# Uchicha.net
KiCad netlist of a schematic drawn in EasyEDA Pro
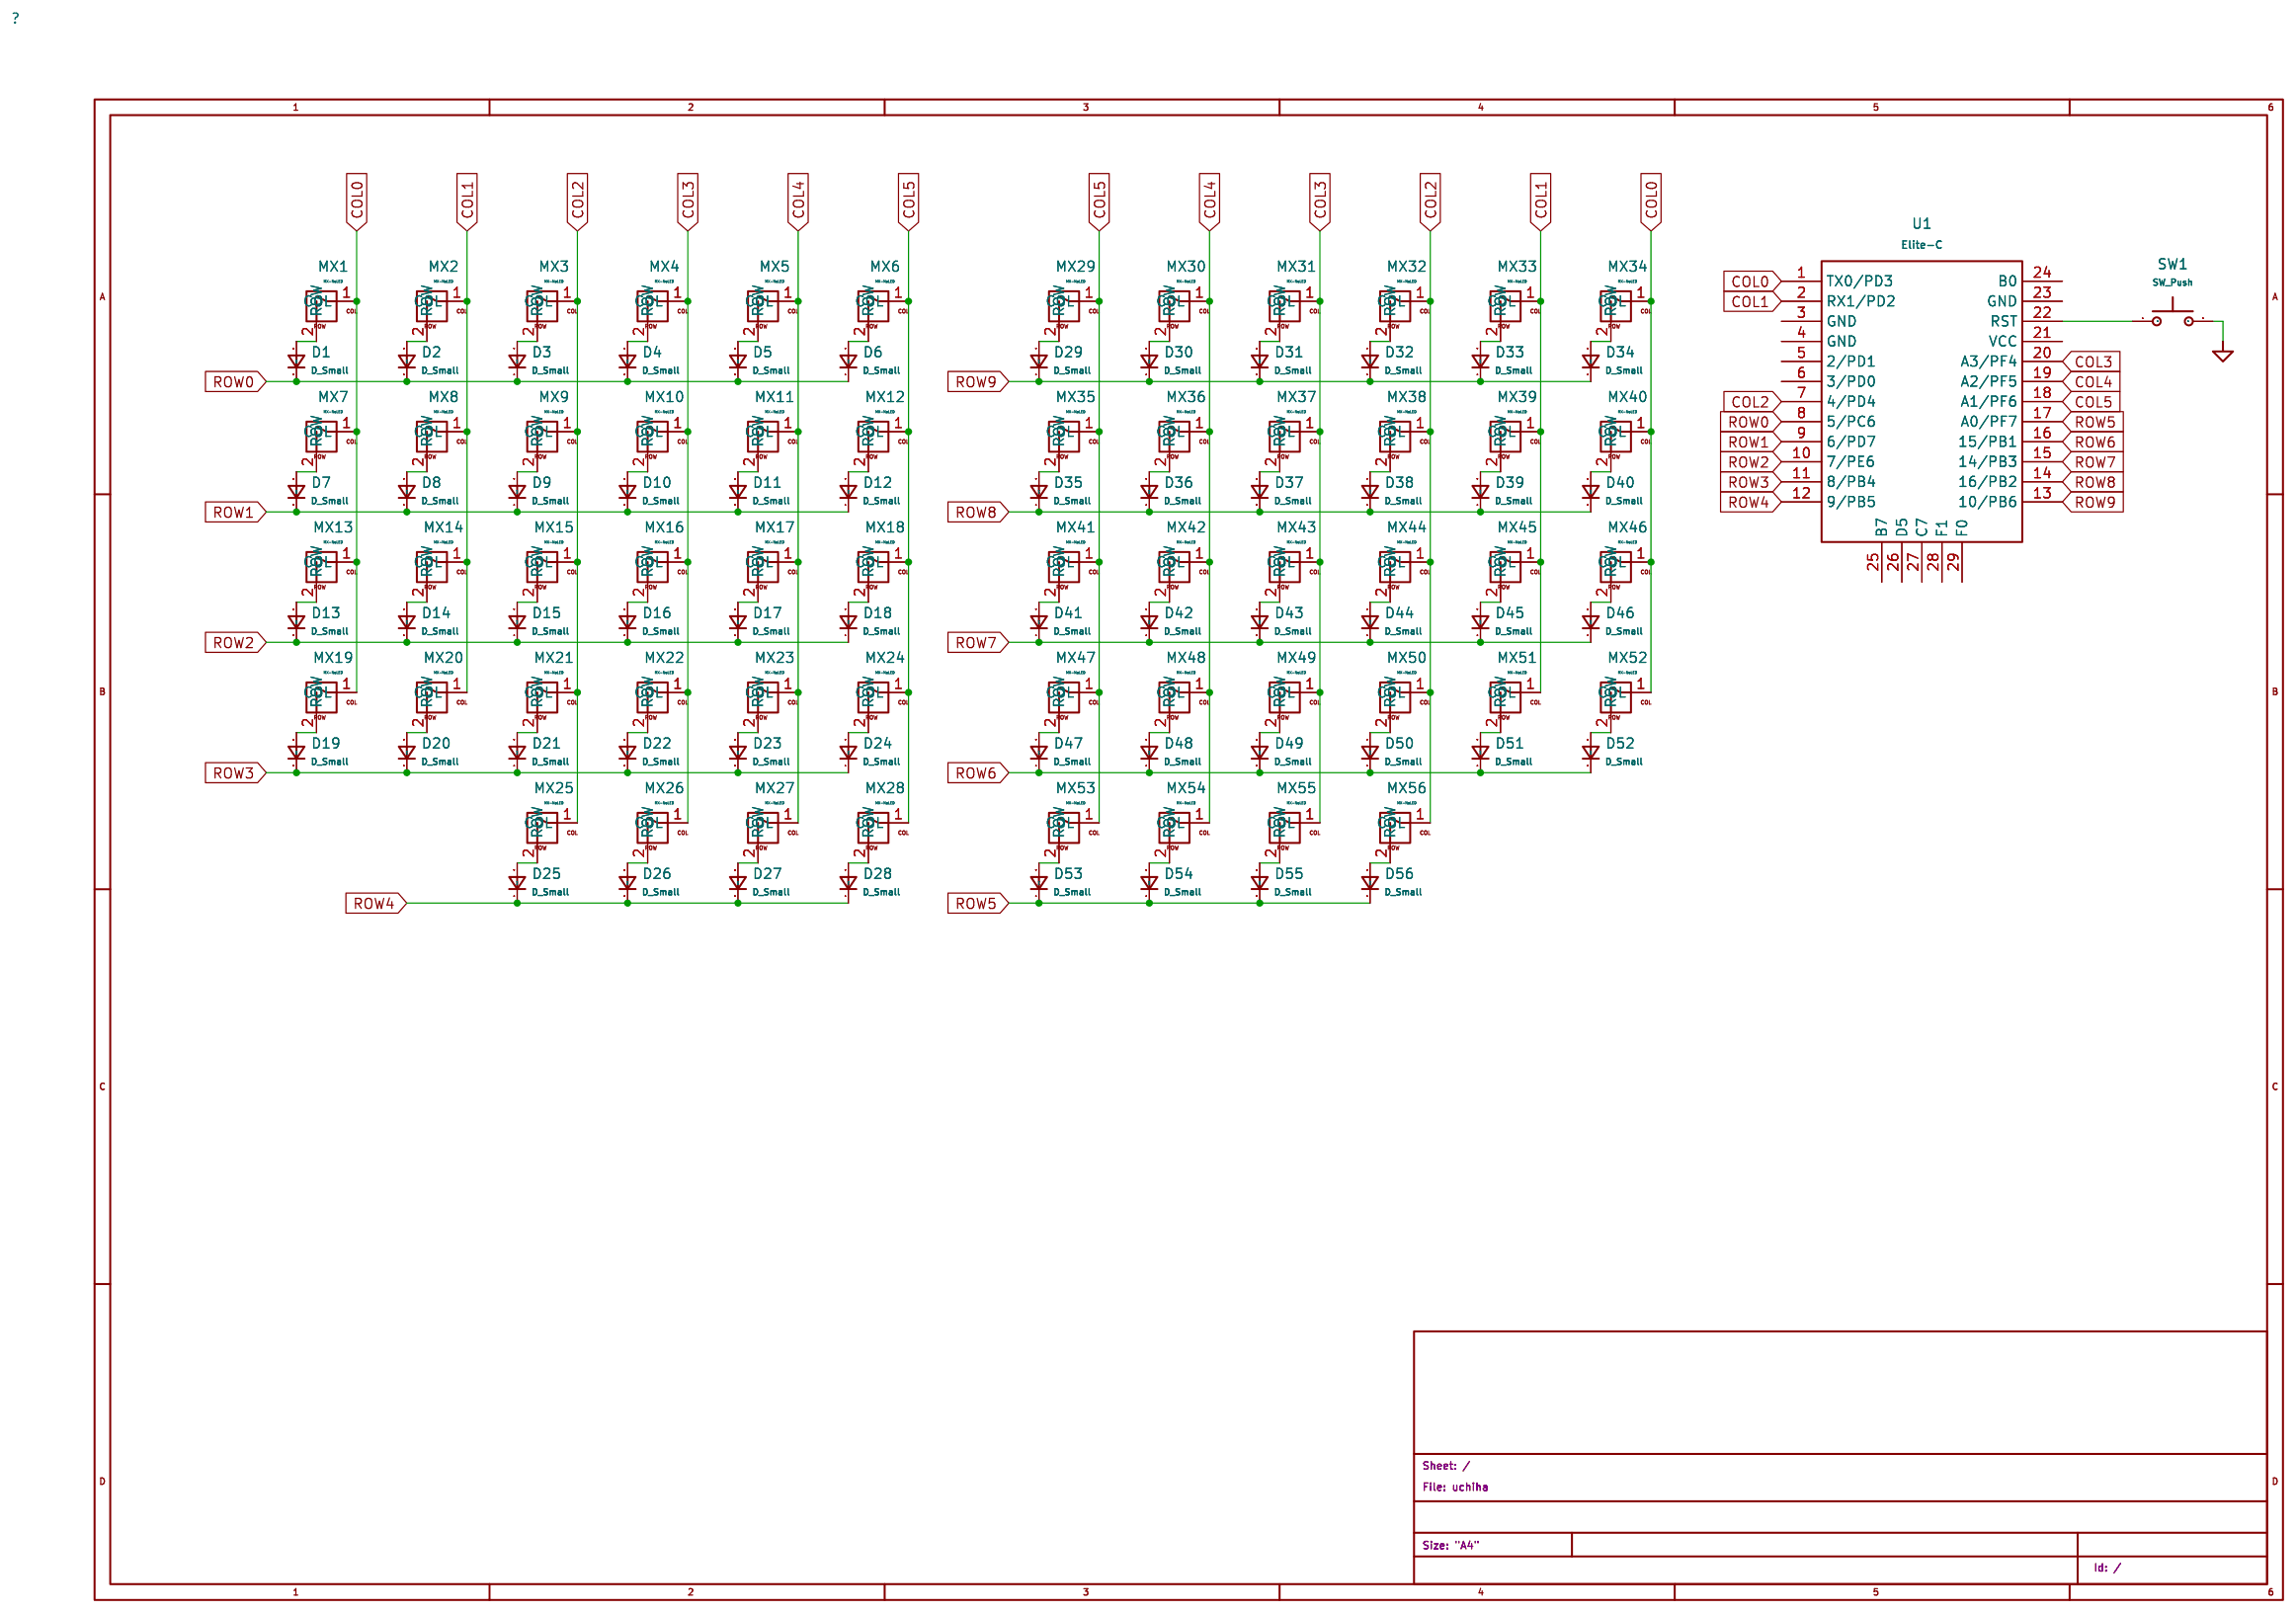
[diagram p0: schematic sheet]

(export (version "E")
  (design (tool "Eeschema 10.0.6"))
  (components
    (comp (ref "D1") (value "D_Small") (libsource (lib "easyedapro") (part "Device_D_Small")))
    (comp (ref "D2") (value "D_Small") (libsource (lib "easyedapro") (part "Device_D_Small")))
    (comp (ref "D3") (value "D_Small") (libsource (lib "easyedapro") (part "Device_D_Small")))
    (comp (ref "D4") (value "D_Small") (libsource (lib "easyedapro") (part "Device_D_Small")))
    (comp (ref "D5") (value "D_Small") (libsource (lib "easyedapro") (part "Device_D_Small")))
    (comp (ref "D6") (value "D_Small") (libsource (lib "easyedapro") (part "Device_D_Small")))
    (comp (ref "D7") (value "D_Small") (libsource (lib "easyedapro") (part "Device_D_Small")))
    (comp (ref "D8") (value "D_Small") (libsource (lib "easyedapro") (part "Device_D_Small")))
    (comp (ref "D9") (value "D_Small") (libsource (lib "easyedapro") (part "Device_D_Small")))
    (comp (ref "D10") (value "D_Small") (libsource (lib "easyedapro") (part "Device_D_Small")))
    (comp (ref "D11") (value "D_Small") (libsource (lib "easyedapro") (part "Device_D_Small")))
    (comp (ref "D12") (value "D_Small") (libsource (lib "easyedapro") (part "Device_D_Small")))
    (comp (ref "D13") (value "D_Small") (libsource (lib "easyedapro") (part "Device_D_Small")))
    (comp (ref "D14") (value "D_Small") (libsource (lib "easyedapro") (part "Device_D_Small")))
    (comp (ref "D15") (value "D_Small") (libsource (lib "easyedapro") (part "Device_D_Small")))
    (comp (ref "D16") (value "D_Small") (libsource (lib "easyedapro") (part "Device_D_Small")))
    (comp (ref "D17") (value "D_Small") (libsource (lib "easyedapro") (part "Device_D_Small")))
    (comp (ref "D18") (value "D_Small") (libsource (lib "easyedapro") (part "Device_D_Small")))
    (comp (ref "D19") (value "D_Small") (libsource (lib "easyedapro") (part "Device_D_Small")))
    (comp (ref "D20") (value "D_Small") (libsource (lib "easyedapro") (part "Device_D_Small")))
    (comp (ref "D21") (value "D_Small") (libsource (lib "easyedapro") (part "Device_D_Small")))
    (comp (ref "D22") (value "D_Small") (libsource (lib "easyedapro") (part "Device_D_Small")))
    (comp (ref "D23") (value "D_Small") (libsource (lib "easyedapro") (part "Device_D_Small")))
    (comp (ref "D24") (value "D_Small") (libsource (lib "easyedapro") (part "Device_D_Small")))
    (comp (ref "D25") (value "D_Small") (libsource (lib "easyedapro") (part "Device_D_Small")))
    (comp (ref "D26") (value "D_Small") (libsource (lib "easyedapro") (part "Device_D_Small")))
    (comp (ref "D27") (value "D_Small") (libsource (lib "easyedapro") (part "Device_D_Small")))
    (comp (ref "D28") (value "D_Small") (libsource (lib "easyedapro") (part "Device_D_Small")))
    (comp (ref "D29") (value "D_Small") (libsource (lib "easyedapro") (part "Device_D_Small")))
    (comp (ref "D30") (value "D_Small") (libsource (lib "easyedapro") (part "Device_D_Small")))
    (comp (ref "D31") (value "D_Small") (libsource (lib "easyedapro") (part "Device_D_Small")))
    (comp (ref "D32") (value "D_Small") (libsource (lib "easyedapro") (part "Device_D_Small")))
    (comp (ref "D33") (value "D_Small") (libsource (lib "easyedapro") (part "Device_D_Small")))
    (comp (ref "D34") (value "D_Small") (libsource (lib "easyedapro") (part "Device_D_Small")))
    (comp (ref "D35") (value "D_Small") (libsource (lib "easyedapro") (part "Device_D_Small")))
    (comp (ref "D36") (value "D_Small") (libsource (lib "easyedapro") (part "Device_D_Small")))
    (comp (ref "D37") (value "D_Small") (libsource (lib "easyedapro") (part "Device_D_Small")))
    (comp (ref "D38") (value "D_Small") (libsource (lib "easyedapro") (part "Device_D_Small")))
    (comp (ref "D39") (value "D_Small") (libsource (lib "easyedapro") (part "Device_D_Small")))
    (comp (ref "D40") (value "D_Small") (libsource (lib "easyedapro") (part "Device_D_Small")))
    (comp (ref "D41") (value "D_Small") (libsource (lib "easyedapro") (part "Device_D_Small")))
    (comp (ref "D42") (value "D_Small") (libsource (lib "easyedapro") (part "Device_D_Small")))
    (comp (ref "D43") (value "D_Small") (libsource (lib "easyedapro") (part "Device_D_Small")))
    (comp (ref "D44") (value "D_Small") (libsource (lib "easyedapro") (part "Device_D_Small")))
    (comp (ref "D45") (value "D_Small") (libsource (lib "easyedapro") (part "Device_D_Small")))
    (comp (ref "D46") (value "D_Small") (libsource (lib "easyedapro") (part "Device_D_Small")))
    (comp (ref "D47") (value "D_Small") (libsource (lib "easyedapro") (part "Device_D_Small")))
    (comp (ref "D48") (value "D_Small") (libsource (lib "easyedapro") (part "Device_D_Small")))
    (comp (ref "D49") (value "D_Small") (libsource (lib "easyedapro") (part "Device_D_Small")))
    (comp (ref "D50") (value "D_Small") (libsource (lib "easyedapro") (part "Device_D_Small")))
    (comp (ref "D51") (value "D_Small") (libsource (lib "easyedapro") (part "Device_D_Small")))
    (comp (ref "D52") (value "D_Small") (libsource (lib "easyedapro") (part "Device_D_Small")))
    (comp (ref "D53") (value "D_Small") (libsource (lib "easyedapro") (part "Device_D_Small")))
    (comp (ref "D54") (value "D_Small") (libsource (lib "easyedapro") (part "Device_D_Small")))
    (comp (ref "D55") (value "D_Small") (libsource (lib "easyedapro") (part "Device_D_Small")))
    (comp (ref "D56") (value "D_Small") (libsource (lib "easyedapro") (part "Device_D_Small")))
    (comp (ref "MX1") (value "MX-NoLED") (libsource (lib "easyedapro") (part "MX_Alps_Hybrid_MX-NoLED")))
    (comp (ref "MX2") (value "MX-NoLED") (libsource (lib "easyedapro") (part "MX_Alps_Hybrid_MX-NoLED")))
    (comp (ref "MX3") (value "MX-NoLED") (libsource (lib "easyedapro") (part "MX_Alps_Hybrid_MX-NoLED")))
    (comp (ref "MX4") (value "MX-NoLED") (libsource (lib "easyedapro") (part "MX_Alps_Hybrid_MX-NoLED")))
    (comp (ref "MX5") (value "MX-NoLED") (libsource (lib "easyedapro") (part "MX_Alps_Hybrid_MX-NoLED")))
    (comp (ref "MX6") (value "MX-NoLED") (libsource (lib "easyedapro") (part "MX_Alps_Hybrid_MX-NoLED")))
    (comp (ref "MX7") (value "MX-NoLED") (libsource (lib "easyedapro") (part "MX_Alps_Hybrid_MX-NoLED")))
    (comp (ref "MX8") (value "MX-NoLED") (libsource (lib "easyedapro") (part "MX_Alps_Hybrid_MX-NoLED")))
    (comp (ref "MX9") (value "MX-NoLED") (libsource (lib "easyedapro") (part "MX_Alps_Hybrid_MX-NoLED")))
    (comp (ref "MX10") (value "MX-NoLED") (libsource (lib "easyedapro") (part "MX_Alps_Hybrid_MX-NoLED")))
    (comp (ref "MX11") (value "MX-NoLED") (libsource (lib "easyedapro") (part "MX_Alps_Hybrid_MX-NoLED")))
    (comp (ref "MX12") (value "MX-NoLED") (libsource (lib "easyedapro") (part "MX_Alps_Hybrid_MX-NoLED")))
    (comp (ref "MX13") (value "MX-NoLED") (libsource (lib "easyedapro") (part "MX_Alps_Hybrid_MX-NoLED")))
    (comp (ref "MX14") (value "MX-NoLED") (libsource (lib "easyedapro") (part "MX_Alps_Hybrid_MX-NoLED")))
    (comp (ref "MX15") (value "MX-NoLED") (libsource (lib "easyedapro") (part "MX_Alps_Hybrid_MX-NoLED")))
    (comp (ref "MX16") (value "MX-NoLED") (libsource (lib "easyedapro") (part "MX_Alps_Hybrid_MX-NoLED")))
    (comp (ref "MX17") (value "MX-NoLED") (libsource (lib "easyedapro") (part "MX_Alps_Hybrid_MX-NoLED")))
    (comp (ref "MX18") (value "MX-NoLED") (libsource (lib "easyedapro") (part "MX_Alps_Hybrid_MX-NoLED")))
    (comp (ref "MX19") (value "MX-NoLED") (libsource (lib "easyedapro") (part "MX_Alps_Hybrid_MX-NoLED")))
    (comp (ref "MX20") (value "MX-NoLED") (libsource (lib "easyedapro") (part "MX_Alps_Hybrid_MX-NoLED")))
    (comp (ref "MX21") (value "MX-NoLED") (libsource (lib "easyedapro") (part "MX_Alps_Hybrid_MX-NoLED")))
    (comp (ref "MX22") (value "MX-NoLED") (libsource (lib "easyedapro") (part "MX_Alps_Hybrid_MX-NoLED")))
    (comp (ref "MX23") (value "MX-NoLED") (libsource (lib "easyedapro") (part "MX_Alps_Hybrid_MX-NoLED")))
    (comp (ref "MX24") (value "MX-NoLED") (libsource (lib "easyedapro") (part "MX_Alps_Hybrid_MX-NoLED")))
    (comp (ref "MX25") (value "MX-NoLED") (libsource (lib "easyedapro") (part "MX_Alps_Hybrid_MX-NoLED")))
    (comp (ref "MX26") (value "MX-NoLED") (libsource (lib "easyedapro") (part "MX_Alps_Hybrid_MX-NoLED")))
    (comp (ref "MX27") (value "MX-NoLED") (libsource (lib "easyedapro") (part "MX_Alps_Hybrid_MX-NoLED")))
    (comp (ref "MX28") (value "MX-NoLED") (libsource (lib "easyedapro") (part "MX_Alps_Hybrid_MX-NoLED")))
    (comp (ref "MX29") (value "MX-NoLED") (libsource (lib "easyedapro") (part "MX_Alps_Hybrid_MX-NoLED")))
    (comp (ref "MX30") (value "MX-NoLED") (libsource (lib "easyedapro") (part "MX_Alps_Hybrid_MX-NoLED")))
    (comp (ref "MX31") (value "MX-NoLED") (libsource (lib "easyedapro") (part "MX_Alps_Hybrid_MX-NoLED")))
    (comp (ref "MX32") (value "MX-NoLED") (libsource (lib "easyedapro") (part "MX_Alps_Hybrid_MX-NoLED")))
    (comp (ref "MX33") (value "MX-NoLED") (libsource (lib "easyedapro") (part "MX_Alps_Hybrid_MX-NoLED")))
    (comp (ref "MX34") (value "MX-NoLED") (libsource (lib "easyedapro") (part "MX_Alps_Hybrid_MX-NoLED")))
    (comp (ref "MX35") (value "MX-NoLED") (libsource (lib "easyedapro") (part "MX_Alps_Hybrid_MX-NoLED")))
    (comp (ref "MX36") (value "MX-NoLED") (libsource (lib "easyedapro") (part "MX_Alps_Hybrid_MX-NoLED")))
    (comp (ref "MX37") (value "MX-NoLED") (libsource (lib "easyedapro") (part "MX_Alps_Hybrid_MX-NoLED")))
    (comp (ref "MX38") (value "MX-NoLED") (libsource (lib "easyedapro") (part "MX_Alps_Hybrid_MX-NoLED")))
    (comp (ref "MX39") (value "MX-NoLED") (libsource (lib "easyedapro") (part "MX_Alps_Hybrid_MX-NoLED")))
    (comp (ref "MX40") (value "MX-NoLED") (libsource (lib "easyedapro") (part "MX_Alps_Hybrid_MX-NoLED")))
    (comp (ref "MX41") (value "MX-NoLED") (libsource (lib "easyedapro") (part "MX_Alps_Hybrid_MX-NoLED")))
    (comp (ref "MX42") (value "MX-NoLED") (libsource (lib "easyedapro") (part "MX_Alps_Hybrid_MX-NoLED")))
    (comp (ref "MX43") (value "MX-NoLED") (libsource (lib "easyedapro") (part "MX_Alps_Hybrid_MX-NoLED")))
    (comp (ref "MX44") (value "MX-NoLED") (libsource (lib "easyedapro") (part "MX_Alps_Hybrid_MX-NoLED")))
    (comp (ref "MX45") (value "MX-NoLED") (libsource (lib "easyedapro") (part "MX_Alps_Hybrid_MX-NoLED")))
    (comp (ref "MX46") (value "MX-NoLED") (libsource (lib "easyedapro") (part "MX_Alps_Hybrid_MX-NoLED")))
    (comp (ref "MX47") (value "MX-NoLED") (libsource (lib "easyedapro") (part "MX_Alps_Hybrid_MX-NoLED")))
    (comp (ref "MX48") (value "MX-NoLED") (libsource (lib "easyedapro") (part "MX_Alps_Hybrid_MX-NoLED")))
    (comp (ref "MX49") (value "MX-NoLED") (libsource (lib "easyedapro") (part "MX_Alps_Hybrid_MX-NoLED")))
    (comp (ref "MX50") (value "MX-NoLED") (libsource (lib "easyedapro") (part "MX_Alps_Hybrid_MX-NoLED")))
    (comp (ref "MX51") (value "MX-NoLED") (libsource (lib "easyedapro") (part "MX_Alps_Hybrid_MX-NoLED")))
    (comp (ref "MX52") (value "MX-NoLED") (libsource (lib "easyedapro") (part "MX_Alps_Hybrid_MX-NoLED")))
    (comp (ref "MX53") (value "MX-NoLED") (libsource (lib "easyedapro") (part "MX_Alps_Hybrid_MX-NoLED")))
    (comp (ref "MX54") (value "MX-NoLED") (libsource (lib "easyedapro") (part "MX_Alps_Hybrid_MX-NoLED")))
    (comp (ref "MX55") (value "MX-NoLED") (libsource (lib "easyedapro") (part "MX_Alps_Hybrid_MX-NoLED")))
    (comp (ref "MX56") (value "MX-NoLED") (libsource (lib "easyedapro") (part "MX_Alps_Hybrid_MX-NoLED")))
    (comp (ref "SW1") (value "SW_Push") (libsource (lib "easyedapro") (part "Switch_SW_Push")))
    (comp (ref "U1") (value "Elite-C") (libsource (lib "easyedapro") (part "keebio_Elite-C")))
  )
  (nets
    (net (code "1") (name "COL0") (class "Default")
      (node (ref "MX1") (pin "1") (pinfunction "COL_1") (pintype "unspecified"))
      (node (ref "MX13") (pin "1") (pinfunction "COL_1") (pintype "unspecified"))
      (node (ref "MX19") (pin "1") (pinfunction "COL_1") (pintype "unspecified"))
      (node (ref "MX34") (pin "1") (pinfunction "COL_1") (pintype "unspecified"))
      (node (ref "MX40") (pin "1") (pinfunction "COL_1") (pintype "unspecified"))
      (node (ref "MX46") (pin "1") (pinfunction "COL_1") (pintype "unspecified"))
      (node (ref "MX52") (pin "1") (pinfunction "COL_1") (pintype "unspecified"))
      (node (ref "MX7") (pin "1") (pinfunction "COL_1") (pintype "unspecified"))
      (node (ref "U1") (pin "1") (pinfunction "TX0/PD3_1") (pintype "input"))
    )
    (net (code "2") (name "COL1") (class "Default")
      (node (ref "MX14") (pin "1") (pinfunction "COL_1") (pintype "unspecified"))
      (node (ref "MX2") (pin "1") (pinfunction "COL_1") (pintype "unspecified"))
      (node (ref "MX20") (pin "1") (pinfunction "COL_1") (pintype "unspecified"))
      (node (ref "MX33") (pin "1") (pinfunction "COL_1") (pintype "unspecified"))
      (node (ref "MX39") (pin "1") (pinfunction "COL_1") (pintype "unspecified"))
      (node (ref "MX45") (pin "1") (pinfunction "COL_1") (pintype "unspecified"))
      (node (ref "MX51") (pin "1") (pinfunction "COL_1") (pintype "unspecified"))
      (node (ref "MX8") (pin "1") (pinfunction "COL_1") (pintype "unspecified"))
      (node (ref "U1") (pin "2") (pinfunction "RX1/PD2_2") (pintype "input"))
    )
    (net (code "3") (name "COL2") (class "Default")
      (node (ref "MX15") (pin "1") (pinfunction "COL_1") (pintype "unspecified"))
      (node (ref "MX21") (pin "1") (pinfunction "COL_1") (pintype "unspecified"))
      (node (ref "MX25") (pin "1") (pinfunction "COL_1") (pintype "unspecified"))
      (node (ref "MX3") (pin "1") (pinfunction "COL_1") (pintype "unspecified"))
      (node (ref "MX32") (pin "1") (pinfunction "COL_1") (pintype "unspecified"))
      (node (ref "MX38") (pin "1") (pinfunction "COL_1") (pintype "unspecified"))
      (node (ref "MX44") (pin "1") (pinfunction "COL_1") (pintype "unspecified"))
      (node (ref "MX50") (pin "1") (pinfunction "COL_1") (pintype "unspecified"))
      (node (ref "MX56") (pin "1") (pinfunction "COL_1") (pintype "unspecified"))
      (node (ref "MX9") (pin "1") (pinfunction "COL_1") (pintype "unspecified"))
      (node (ref "U1") (pin "7") (pinfunction "4/PD4_7") (pintype "input"))
    )
    (net (code "4") (name "COL3") (class "Default")
      (node (ref "MX10") (pin "1") (pinfunction "COL_1") (pintype "unspecified"))
      (node (ref "MX16") (pin "1") (pinfunction "COL_1") (pintype "unspecified"))
      (node (ref "MX22") (pin "1") (pinfunction "COL_1") (pintype "unspecified"))
      (node (ref "MX26") (pin "1") (pinfunction "COL_1") (pintype "unspecified"))
      (node (ref "MX31") (pin "1") (pinfunction "COL_1") (pintype "unspecified"))
      (node (ref "MX37") (pin "1") (pinfunction "COL_1") (pintype "unspecified"))
      (node (ref "MX4") (pin "1") (pinfunction "COL_1") (pintype "unspecified"))
      (node (ref "MX43") (pin "1") (pinfunction "COL_1") (pintype "unspecified"))
      (node (ref "MX49") (pin "1") (pinfunction "COL_1") (pintype "unspecified"))
      (node (ref "MX55") (pin "1") (pinfunction "COL_1") (pintype "unspecified"))
      (node (ref "U1") (pin "20") (pinfunction "A3/PF4_20") (pintype "input"))
    )
    (net (code "5") (name "COL4") (class "Default")
      (node (ref "MX11") (pin "1") (pinfunction "COL_1") (pintype "unspecified"))
      (node (ref "MX17") (pin "1") (pinfunction "COL_1") (pintype "unspecified"))
      (node (ref "MX23") (pin "1") (pinfunction "COL_1") (pintype "unspecified"))
      (node (ref "MX27") (pin "1") (pinfunction "COL_1") (pintype "unspecified"))
      (node (ref "MX30") (pin "1") (pinfunction "COL_1") (pintype "unspecified"))
      (node (ref "MX36") (pin "1") (pinfunction "COL_1") (pintype "unspecified"))
      (node (ref "MX42") (pin "1") (pinfunction "COL_1") (pintype "unspecified"))
      (node (ref "MX48") (pin "1") (pinfunction "COL_1") (pintype "unspecified"))
      (node (ref "MX5") (pin "1") (pinfunction "COL_1") (pintype "unspecified"))
      (node (ref "MX54") (pin "1") (pinfunction "COL_1") (pintype "unspecified"))
      (node (ref "U1") (pin "19") (pinfunction "A2/PF5_19") (pintype "input"))
    )
    (net (code "6") (name "COL5") (class "Default")
      (node (ref "MX12") (pin "1") (pinfunction "COL_1") (pintype "unspecified"))
      (node (ref "MX18") (pin "1") (pinfunction "COL_1") (pintype "unspecified"))
      (node (ref "MX24") (pin "1") (pinfunction "COL_1") (pintype "unspecified"))
      (node (ref "MX28") (pin "1") (pinfunction "COL_1") (pintype "unspecified"))
      (node (ref "MX29") (pin "1") (pinfunction "COL_1") (pintype "unspecified"))
      (node (ref "MX35") (pin "1") (pinfunction "COL_1") (pintype "unspecified"))
      (node (ref "MX41") (pin "1") (pinfunction "COL_1") (pintype "unspecified"))
      (node (ref "MX47") (pin "1") (pinfunction "COL_1") (pintype "unspecified"))
      (node (ref "MX53") (pin "1") (pinfunction "COL_1") (pintype "unspecified"))
      (node (ref "MX6") (pin "1") (pinfunction "COL_1") (pintype "unspecified"))
      (node (ref "U1") (pin "18") (pinfunction "A1/PF6_18") (pintype "input"))
    )
    (net (code "7") (name "Net-(D1-A)") (class "Default")
      (node (ref "D1") (pin "2") (pinfunction "A_2") (pintype "unspecified"))
      (node (ref "MX1") (pin "2") (pinfunction "ROW_2") (pintype "unspecified"))
    )
    (net (code "8") (name "Net-(D2-A)") (class "Default")
      (node (ref "D2") (pin "2") (pinfunction "A_2") (pintype "unspecified"))
      (node (ref "MX2") (pin "2") (pinfunction "ROW_2") (pintype "unspecified"))
    )
    (net (code "9") (name "Net-(D3-A)") (class "Default")
      (node (ref "D3") (pin "2") (pinfunction "A_2") (pintype "unspecified"))
      (node (ref "MX3") (pin "2") (pinfunction "ROW_2") (pintype "unspecified"))
    )
    (net (code "10") (name "Net-(D4-A)") (class "Default")
      (node (ref "D4") (pin "2") (pinfunction "A_2") (pintype "unspecified"))
      (node (ref "MX4") (pin "2") (pinfunction "ROW_2") (pintype "unspecified"))
    )
    (net (code "11") (name "Net-(D5-A)") (class "Default")
      (node (ref "D5") (pin "2") (pinfunction "A_2") (pintype "unspecified"))
      (node (ref "MX5") (pin "2") (pinfunction "ROW_2") (pintype "unspecified"))
    )
    (net (code "12") (name "Net-(D6-A)") (class "Default")
      (node (ref "D6") (pin "2") (pinfunction "A_2") (pintype "unspecified"))
      (node (ref "MX6") (pin "2") (pinfunction "ROW_2") (pintype "unspecified"))
    )
    (net (code "13") (name "Net-(D7-A)") (class "Default")
      (node (ref "D7") (pin "2") (pinfunction "A_2") (pintype "unspecified"))
      (node (ref "MX7") (pin "2") (pinfunction "ROW_2") (pintype "unspecified"))
    )
    (net (code "14") (name "Net-(D8-A)") (class "Default")
      (node (ref "D8") (pin "2") (pinfunction "A_2") (pintype "unspecified"))
      (node (ref "MX8") (pin "2") (pinfunction "ROW_2") (pintype "unspecified"))
    )
    (net (code "15") (name "Net-(D9-A)") (class "Default")
      (node (ref "D9") (pin "2") (pinfunction "A_2") (pintype "unspecified"))
      (node (ref "MX9") (pin "2") (pinfunction "ROW_2") (pintype "unspecified"))
    )
    (net (code "16") (name "Net-(D10-A)") (class "Default")
      (node (ref "D10") (pin "2") (pinfunction "A_2") (pintype "unspecified"))
      (node (ref "MX10") (pin "2") (pinfunction "ROW_2") (pintype "unspecified"))
    )
    (net (code "17") (name "Net-(D11-A)") (class "Default")
      (node (ref "D11") (pin "2") (pinfunction "A_2") (pintype "unspecified"))
      (node (ref "MX11") (pin "2") (pinfunction "ROW_2") (pintype "unspecified"))
    )
    (net (code "18") (name "Net-(D12-A)") (class "Default")
      (node (ref "D12") (pin "2") (pinfunction "A_2") (pintype "unspecified"))
      (node (ref "MX12") (pin "2") (pinfunction "ROW_2") (pintype "unspecified"))
    )
    (net (code "19") (name "Net-(D13-A)") (class "Default")
      (node (ref "D13") (pin "2") (pinfunction "A_2") (pintype "unspecified"))
      (node (ref "MX13") (pin "2") (pinfunction "ROW_2") (pintype "unspecified"))
    )
    (net (code "20") (name "Net-(D14-A)") (class "Default")
      (node (ref "D14") (pin "2") (pinfunction "A_2") (pintype "unspecified"))
      (node (ref "MX14") (pin "2") (pinfunction "ROW_2") (pintype "unspecified"))
    )
    (net (code "21") (name "Net-(D15-A)") (class "Default")
      (node (ref "D15") (pin "2") (pinfunction "A_2") (pintype "unspecified"))
      (node (ref "MX15") (pin "2") (pinfunction "ROW_2") (pintype "unspecified"))
    )
    (net (code "22") (name "Net-(D16-A)") (class "Default")
      (node (ref "D16") (pin "2") (pinfunction "A_2") (pintype "unspecified"))
      (node (ref "MX16") (pin "2") (pinfunction "ROW_2") (pintype "unspecified"))
    )
    (net (code "23") (name "Net-(D17-A)") (class "Default")
      (node (ref "D17") (pin "2") (pinfunction "A_2") (pintype "unspecified"))
      (node (ref "MX17") (pin "2") (pinfunction "ROW_2") (pintype "unspecified"))
    )
    (net (code "24") (name "Net-(D18-A)") (class "Default")
      (node (ref "D18") (pin "2") (pinfunction "A_2") (pintype "unspecified"))
      (node (ref "MX18") (pin "2") (pinfunction "ROW_2") (pintype "unspecified"))
    )
    (net (code "25") (name "Net-(D19-A)") (class "Default")
      (node (ref "D19") (pin "2") (pinfunction "A_2") (pintype "unspecified"))
      (node (ref "MX19") (pin "2") (pinfunction "ROW_2") (pintype "unspecified"))
    )
    (net (code "26") (name "Net-(D20-A)") (class "Default")
      (node (ref "D20") (pin "2") (pinfunction "A_2") (pintype "unspecified"))
      (node (ref "MX20") (pin "2") (pinfunction "ROW_2") (pintype "unspecified"))
    )
    (net (code "27") (name "Net-(D21-A)") (class "Default")
      (node (ref "D21") (pin "2") (pinfunction "A_2") (pintype "unspecified"))
      (node (ref "MX21") (pin "2") (pinfunction "ROW_2") (pintype "unspecified"))
    )
    (net (code "28") (name "Net-(D22-A)") (class "Default")
      (node (ref "D22") (pin "2") (pinfunction "A_2") (pintype "unspecified"))
      (node (ref "MX22") (pin "2") (pinfunction "ROW_2") (pintype "unspecified"))
    )
    (net (code "29") (name "Net-(D23-A)") (class "Default")
      (node (ref "D23") (pin "2") (pinfunction "A_2") (pintype "unspecified"))
      (node (ref "MX23") (pin "2") (pinfunction "ROW_2") (pintype "unspecified"))
    )
    (net (code "30") (name "Net-(D24-A)") (class "Default")
      (node (ref "D24") (pin "2") (pinfunction "A_2") (pintype "unspecified"))
      (node (ref "MX24") (pin "2") (pinfunction "ROW_2") (pintype "unspecified"))
    )
    (net (code "31") (name "Net-(D25-A)") (class "Default")
      (node (ref "D25") (pin "2") (pinfunction "A_2") (pintype "unspecified"))
      (node (ref "MX25") (pin "2") (pinfunction "ROW_2") (pintype "unspecified"))
    )
    (net (code "32") (name "Net-(D26-A)") (class "Default")
      (node (ref "D26") (pin "2") (pinfunction "A_2") (pintype "unspecified"))
      (node (ref "MX26") (pin "2") (pinfunction "ROW_2") (pintype "unspecified"))
    )
    (net (code "33") (name "Net-(D27-A)") (class "Default")
      (node (ref "D27") (pin "2") (pinfunction "A_2") (pintype "unspecified"))
      (node (ref "MX27") (pin "2") (pinfunction "ROW_2") (pintype "unspecified"))
    )
    (net (code "34") (name "Net-(D28-A)") (class "Default")
      (node (ref "D28") (pin "2") (pinfunction "A_2") (pintype "unspecified"))
      (node (ref "MX28") (pin "2") (pinfunction "ROW_2") (pintype "unspecified"))
    )
    (net (code "35") (name "Net-(D29-A)") (class "Default")
      (node (ref "D29") (pin "2") (pinfunction "A_2") (pintype "unspecified"))
      (node (ref "MX29") (pin "2") (pinfunction "ROW_2") (pintype "unspecified"))
    )
    (net (code "36") (name "Net-(D30-A)") (class "Default")
      (node (ref "D30") (pin "2") (pinfunction "A_2") (pintype "unspecified"))
      (node (ref "MX30") (pin "2") (pinfunction "ROW_2") (pintype "unspecified"))
    )
    (net (code "37") (name "Net-(D31-A)") (class "Default")
      (node (ref "D31") (pin "2") (pinfunction "A_2") (pintype "unspecified"))
      (node (ref "MX31") (pin "2") (pinfunction "ROW_2") (pintype "unspecified"))
    )
    (net (code "38") (name "Net-(D32-A)") (class "Default")
      (node (ref "D32") (pin "2") (pinfunction "A_2") (pintype "unspecified"))
      (node (ref "MX32") (pin "2") (pinfunction "ROW_2") (pintype "unspecified"))
    )
    (net (code "39") (name "Net-(D33-A)") (class "Default")
      (node (ref "D33") (pin "2") (pinfunction "A_2") (pintype "unspecified"))
      (node (ref "MX33") (pin "2") (pinfunction "ROW_2") (pintype "unspecified"))
    )
    (net (code "40") (name "Net-(D34-A)") (class "Default")
      (node (ref "D34") (pin "2") (pinfunction "A_2") (pintype "unspecified"))
      (node (ref "MX34") (pin "2") (pinfunction "ROW_2") (pintype "unspecified"))
    )
    (net (code "41") (name "Net-(D35-A)") (class "Default")
      (node (ref "D35") (pin "2") (pinfunction "A_2") (pintype "unspecified"))
      (node (ref "MX35") (pin "2") (pinfunction "ROW_2") (pintype "unspecified"))
    )
    (net (code "42") (name "Net-(D36-A)") (class "Default")
      (node (ref "D36") (pin "2") (pinfunction "A_2") (pintype "unspecified"))
      (node (ref "MX36") (pin "2") (pinfunction "ROW_2") (pintype "unspecified"))
    )
    (net (code "43") (name "Net-(D37-A)") (class "Default")
      (node (ref "D37") (pin "2") (pinfunction "A_2") (pintype "unspecified"))
      (node (ref "MX37") (pin "2") (pinfunction "ROW_2") (pintype "unspecified"))
    )
    (net (code "44") (name "Net-(D38-A)") (class "Default")
      (node (ref "D38") (pin "2") (pinfunction "A_2") (pintype "unspecified"))
      (node (ref "MX38") (pin "2") (pinfunction "ROW_2") (pintype "unspecified"))
    )
    (net (code "45") (name "Net-(D39-A)") (class "Default")
      (node (ref "D39") (pin "2") (pinfunction "A_2") (pintype "unspecified"))
      (node (ref "MX39") (pin "2") (pinfunction "ROW_2") (pintype "unspecified"))
    )
    (net (code "46") (name "Net-(D40-A)") (class "Default")
      (node (ref "D40") (pin "2") (pinfunction "A_2") (pintype "unspecified"))
      (node (ref "MX40") (pin "2") (pinfunction "ROW_2") (pintype "unspecified"))
    )
    (net (code "47") (name "Net-(D41-A)") (class "Default")
      (node (ref "D41") (pin "2") (pinfunction "A_2") (pintype "unspecified"))
      (node (ref "MX41") (pin "2") (pinfunction "ROW_2") (pintype "unspecified"))
    )
    (net (code "48") (name "Net-(D42-A)") (class "Default")
      (node (ref "D42") (pin "2") (pinfunction "A_2") (pintype "unspecified"))
      (node (ref "MX42") (pin "2") (pinfunction "ROW_2") (pintype "unspecified"))
    )
    (net (code "49") (name "Net-(D43-A)") (class "Default")
      (node (ref "D43") (pin "2") (pinfunction "A_2") (pintype "unspecified"))
      (node (ref "MX43") (pin "2") (pinfunction "ROW_2") (pintype "unspecified"))
    )
    (net (code "50") (name "Net-(D44-A)") (class "Default")
      (node (ref "D44") (pin "2") (pinfunction "A_2") (pintype "unspecified"))
      (node (ref "MX44") (pin "2") (pinfunction "ROW_2") (pintype "unspecified"))
    )
    (net (code "51") (name "Net-(D45-A)") (class "Default")
      (node (ref "D45") (pin "2") (pinfunction "A_2") (pintype "unspecified"))
      (node (ref "MX45") (pin "2") (pinfunction "ROW_2") (pintype "unspecified"))
    )
    (net (code "52") (name "Net-(D46-A)") (class "Default")
      (node (ref "D46") (pin "2") (pinfunction "A_2") (pintype "unspecified"))
      (node (ref "MX46") (pin "2") (pinfunction "ROW_2") (pintype "unspecified"))
    )
    (net (code "53") (name "Net-(D47-A)") (class "Default")
      (node (ref "D47") (pin "2") (pinfunction "A_2") (pintype "unspecified"))
      (node (ref "MX47") (pin "2") (pinfunction "ROW_2") (pintype "unspecified"))
    )
    (net (code "54") (name "Net-(D48-A)") (class "Default")
      (node (ref "D48") (pin "2") (pinfunction "A_2") (pintype "unspecified"))
      (node (ref "MX48") (pin "2") (pinfunction "ROW_2") (pintype "unspecified"))
    )
    (net (code "55") (name "Net-(D49-A)") (class "Default")
      (node (ref "D49") (pin "2") (pinfunction "A_2") (pintype "unspecified"))
      (node (ref "MX49") (pin "2") (pinfunction "ROW_2") (pintype "unspecified"))
    )
    (net (code "56") (name "Net-(D50-A)") (class "Default")
      (node (ref "D50") (pin "2") (pinfunction "A_2") (pintype "unspecified"))
      (node (ref "MX50") (pin "2") (pinfunction "ROW_2") (pintype "unspecified"))
    )
    (net (code "57") (name "Net-(D51-A)") (class "Default")
      (node (ref "D51") (pin "2") (pinfunction "A_2") (pintype "unspecified"))
      (node (ref "MX51") (pin "2") (pinfunction "ROW_2") (pintype "unspecified"))
    )
    (net (code "58") (name "Net-(D52-A)") (class "Default")
      (node (ref "D52") (pin "2") (pinfunction "A_2") (pintype "unspecified"))
      (node (ref "MX52") (pin "2") (pinfunction "ROW_2") (pintype "unspecified"))
    )
    (net (code "59") (name "Net-(D53-A)") (class "Default")
      (node (ref "D53") (pin "2") (pinfunction "A_2") (pintype "unspecified"))
      (node (ref "MX53") (pin "2") (pinfunction "ROW_2") (pintype "unspecified"))
    )
    (net (code "60") (name "Net-(D54-A)") (class "Default")
      (node (ref "D54") (pin "2") (pinfunction "A_2") (pintype "unspecified"))
      (node (ref "MX54") (pin "2") (pinfunction "ROW_2") (pintype "unspecified"))
    )
    (net (code "61") (name "Net-(D55-A)") (class "Default")
      (node (ref "D55") (pin "2") (pinfunction "A_2") (pintype "unspecified"))
      (node (ref "MX55") (pin "2") (pinfunction "ROW_2") (pintype "unspecified"))
    )
    (net (code "62") (name "Net-(D56-A)") (class "Default")
      (node (ref "D56") (pin "2") (pinfunction "A_2") (pintype "unspecified"))
      (node (ref "MX56") (pin "2") (pinfunction "ROW_2") (pintype "unspecified"))
    )
    (net (code "63") (name "Net-(U1-RST)") (class "Default")
      (node (ref "SW1") (pin "1") (pinfunction "1_1") (pintype "unspecified"))
      (node (ref "U1") (pin "22") (pinfunction "RST_22") (pintype "input"))
    )
    (net (code "64") (name "POWER_GND") (class "Default")
      (node (ref "SW1") (pin "2") (pinfunction "2_2") (pintype "unspecified"))
    )
    (net (code "65") (name "ROW0") (class "Default")
      (node (ref "D1") (pin "1") (pinfunction "K_1") (pintype "unspecified"))
      (node (ref "D2") (pin "1") (pinfunction "K_1") (pintype "unspecified"))
      (node (ref "D3") (pin "1") (pinfunction "K_1") (pintype "unspecified"))
      (node (ref "D4") (pin "1") (pinfunction "K_1") (pintype "unspecified"))
      (node (ref "D5") (pin "1") (pinfunction "K_1") (pintype "unspecified"))
      (node (ref "D6") (pin "1") (pinfunction "K_1") (pintype "unspecified"))
      (node (ref "U1") (pin "8") (pinfunction "5/PC6_8") (pintype "input"))
    )
    (net (code "66") (name "ROW1") (class "Default")
      (node (ref "D10") (pin "1") (pinfunction "K_1") (pintype "unspecified"))
      (node (ref "D11") (pin "1") (pinfunction "K_1") (pintype "unspecified"))
      (node (ref "D12") (pin "1") (pinfunction "K_1") (pintype "unspecified"))
      (node (ref "D7") (pin "1") (pinfunction "K_1") (pintype "unspecified"))
      (node (ref "D8") (pin "1") (pinfunction "K_1") (pintype "unspecified"))
      (node (ref "D9") (pin "1") (pinfunction "K_1") (pintype "unspecified"))
      (node (ref "U1") (pin "9") (pinfunction "6/PD7_9") (pintype "input"))
    )
    (net (code "67") (name "ROW2") (class "Default")
      (node (ref "D13") (pin "1") (pinfunction "K_1") (pintype "unspecified"))
      (node (ref "D14") (pin "1") (pinfunction "K_1") (pintype "unspecified"))
      (node (ref "D15") (pin "1") (pinfunction "K_1") (pintype "unspecified"))
      (node (ref "D16") (pin "1") (pinfunction "K_1") (pintype "unspecified"))
      (node (ref "D17") (pin "1") (pinfunction "K_1") (pintype "unspecified"))
      (node (ref "D18") (pin "1") (pinfunction "K_1") (pintype "unspecified"))
      (node (ref "U1") (pin "10") (pinfunction "7/PE6_10") (pintype "input"))
    )
    (net (code "68") (name "ROW3") (class "Default")
      (node (ref "D19") (pin "1") (pinfunction "K_1") (pintype "unspecified"))
      (node (ref "D20") (pin "1") (pinfunction "K_1") (pintype "unspecified"))
      (node (ref "D21") (pin "1") (pinfunction "K_1") (pintype "unspecified"))
      (node (ref "D22") (pin "1") (pinfunction "K_1") (pintype "unspecified"))
      (node (ref "D23") (pin "1") (pinfunction "K_1") (pintype "unspecified"))
      (node (ref "D24") (pin "1") (pinfunction "K_1") (pintype "unspecified"))
      (node (ref "U1") (pin "11") (pinfunction "8/PB4_11") (pintype "input"))
    )
    (net (code "69") (name "ROW4") (class "Default")
      (node (ref "D25") (pin "1") (pinfunction "K_1") (pintype "unspecified"))
      (node (ref "D26") (pin "1") (pinfunction "K_1") (pintype "unspecified"))
      (node (ref "D27") (pin "1") (pinfunction "K_1") (pintype "unspecified"))
      (node (ref "D28") (pin "1") (pinfunction "K_1") (pintype "unspecified"))
      (node (ref "U1") (pin "12") (pinfunction "9/PB5_12") (pintype "input"))
    )
    (net (code "70") (name "ROW5") (class "Default")
      (node (ref "D53") (pin "1") (pinfunction "K_1") (pintype "unspecified"))
      (node (ref "D54") (pin "1") (pinfunction "K_1") (pintype "unspecified"))
      (node (ref "D55") (pin "1") (pinfunction "K_1") (pintype "unspecified"))
      (node (ref "D56") (pin "1") (pinfunction "K_1") (pintype "unspecified"))
      (node (ref "U1") (pin "17") (pinfunction "A0/PF7_17") (pintype "input"))
    )
    (net (code "71") (name "ROW6") (class "Default")
      (node (ref "D47") (pin "1") (pinfunction "K_1") (pintype "unspecified"))
      (node (ref "D48") (pin "1") (pinfunction "K_1") (pintype "unspecified"))
      (node (ref "D49") (pin "1") (pinfunction "K_1") (pintype "unspecified"))
      (node (ref "D50") (pin "1") (pinfunction "K_1") (pintype "unspecified"))
      (node (ref "D51") (pin "1") (pinfunction "K_1") (pintype "unspecified"))
      (node (ref "D52") (pin "1") (pinfunction "K_1") (pintype "unspecified"))
      (node (ref "U1") (pin "16") (pinfunction "15/PB1_16") (pintype "input"))
    )
    (net (code "72") (name "ROW7") (class "Default")
      (node (ref "D41") (pin "1") (pinfunction "K_1") (pintype "unspecified"))
      (node (ref "D42") (pin "1") (pinfunction "K_1") (pintype "unspecified"))
      (node (ref "D43") (pin "1") (pinfunction "K_1") (pintype "unspecified"))
      (node (ref "D44") (pin "1") (pinfunction "K_1") (pintype "unspecified"))
      (node (ref "D45") (pin "1") (pinfunction "K_1") (pintype "unspecified"))
      (node (ref "D46") (pin "1") (pinfunction "K_1") (pintype "unspecified"))
      (node (ref "U1") (pin "15") (pinfunction "14/PB3_15") (pintype "input"))
    )
    (net (code "73") (name "ROW8") (class "Default")
      (node (ref "D35") (pin "1") (pinfunction "K_1") (pintype "unspecified"))
      (node (ref "D36") (pin "1") (pinfunction "K_1") (pintype "unspecified"))
      (node (ref "D37") (pin "1") (pinfunction "K_1") (pintype "unspecified"))
      (node (ref "D38") (pin "1") (pinfunction "K_1") (pintype "unspecified"))
      (node (ref "D39") (pin "1") (pinfunction "K_1") (pintype "unspecified"))
      (node (ref "D40") (pin "1") (pinfunction "K_1") (pintype "unspecified"))
      (node (ref "U1") (pin "14") (pinfunction "16/PB2_14") (pintype "input"))
    )
    (net (code "74") (name "ROW9") (class "Default")
      (node (ref "D29") (pin "1") (pinfunction "K_1") (pintype "unspecified"))
      (node (ref "D30") (pin "1") (pinfunction "K_1") (pintype "unspecified"))
      (node (ref "D31") (pin "1") (pinfunction "K_1") (pintype "unspecified"))
      (node (ref "D32") (pin "1") (pinfunction "K_1") (pintype "unspecified"))
      (node (ref "D33") (pin "1") (pinfunction "K_1") (pintype "unspecified"))
      (node (ref "D34") (pin "1") (pinfunction "K_1") (pintype "unspecified"))
      (node (ref "U1") (pin "13") (pinfunction "10/PB6_13") (pintype "input"))
    )
    (net (code "75") (name "unconnected-(U1-2{slash}PD1-Pad5)") (class "Default")
      (node (ref "U1") (pin "5") (pinfunction "2/PD1_5") (pintype "input"))
    )
    (net (code "76") (name "unconnected-(U1-3{slash}PD0-Pad6)") (class "Default")
      (node (ref "U1") (pin "6") (pinfunction "3/PD0_6") (pintype "input"))
    )
    (net (code "77") (name "unconnected-(U1-B0-Pad24)") (class "Default")
      (node (ref "U1") (pin "24") (pinfunction "B0_24") (pintype "input"))
    )
    (net (code "78") (name "unconnected-(U1-B7-Pad25)") (class "Default")
      (node (ref "U1") (pin "25") (pinfunction "B7_25") (pintype "input"))
    )
    (net (code "79") (name "unconnected-(U1-C7-Pad27)") (class "Default")
      (node (ref "U1") (pin "27") (pinfunction "C7_27") (pintype "input"))
    )
    (net (code "80") (name "unconnected-(U1-D5-Pad26)") (class "Default")
      (node (ref "U1") (pin "26") (pinfunction "D5_26") (pintype "input"))
    )
    (net (code "81") (name "unconnected-(U1-F0-Pad29)") (class "Default")
      (node (ref "U1") (pin "29") (pinfunction "F0_29") (pintype "input"))
    )
    (net (code "82") (name "unconnected-(U1-F1-Pad28)") (class "Default")
      (node (ref "U1") (pin "28") (pinfunction "F1_28") (pintype "input"))
    )
    (net (code "83") (name "unconnected-(U1-GND-Pad3)") (class "Default")
      (node (ref "U1") (pin "3") (pinfunction "GND_3") (pintype "input"))
    )
    (net (code "84") (name "unconnected-(U1-GND-Pad4)") (class "Default")
      (node (ref "U1") (pin "4") (pinfunction "GND_4") (pintype "input"))
    )
    (net (code "85") (name "unconnected-(U1-GND-Pad23)") (class "Default")
      (node (ref "U1") (pin "23") (pinfunction "GND_23") (pintype "input"))
    )
    (net (code "86") (name "unconnected-(U1-VCC-Pad21)") (class "Default")
      (node (ref "U1") (pin "21") (pinfunction "VCC_21") (pintype "input"))
    )
  )
)
